# blot-control-board_easyEDA-schematic.net
KiCad netlist of a schematic drawn in EasyEDA
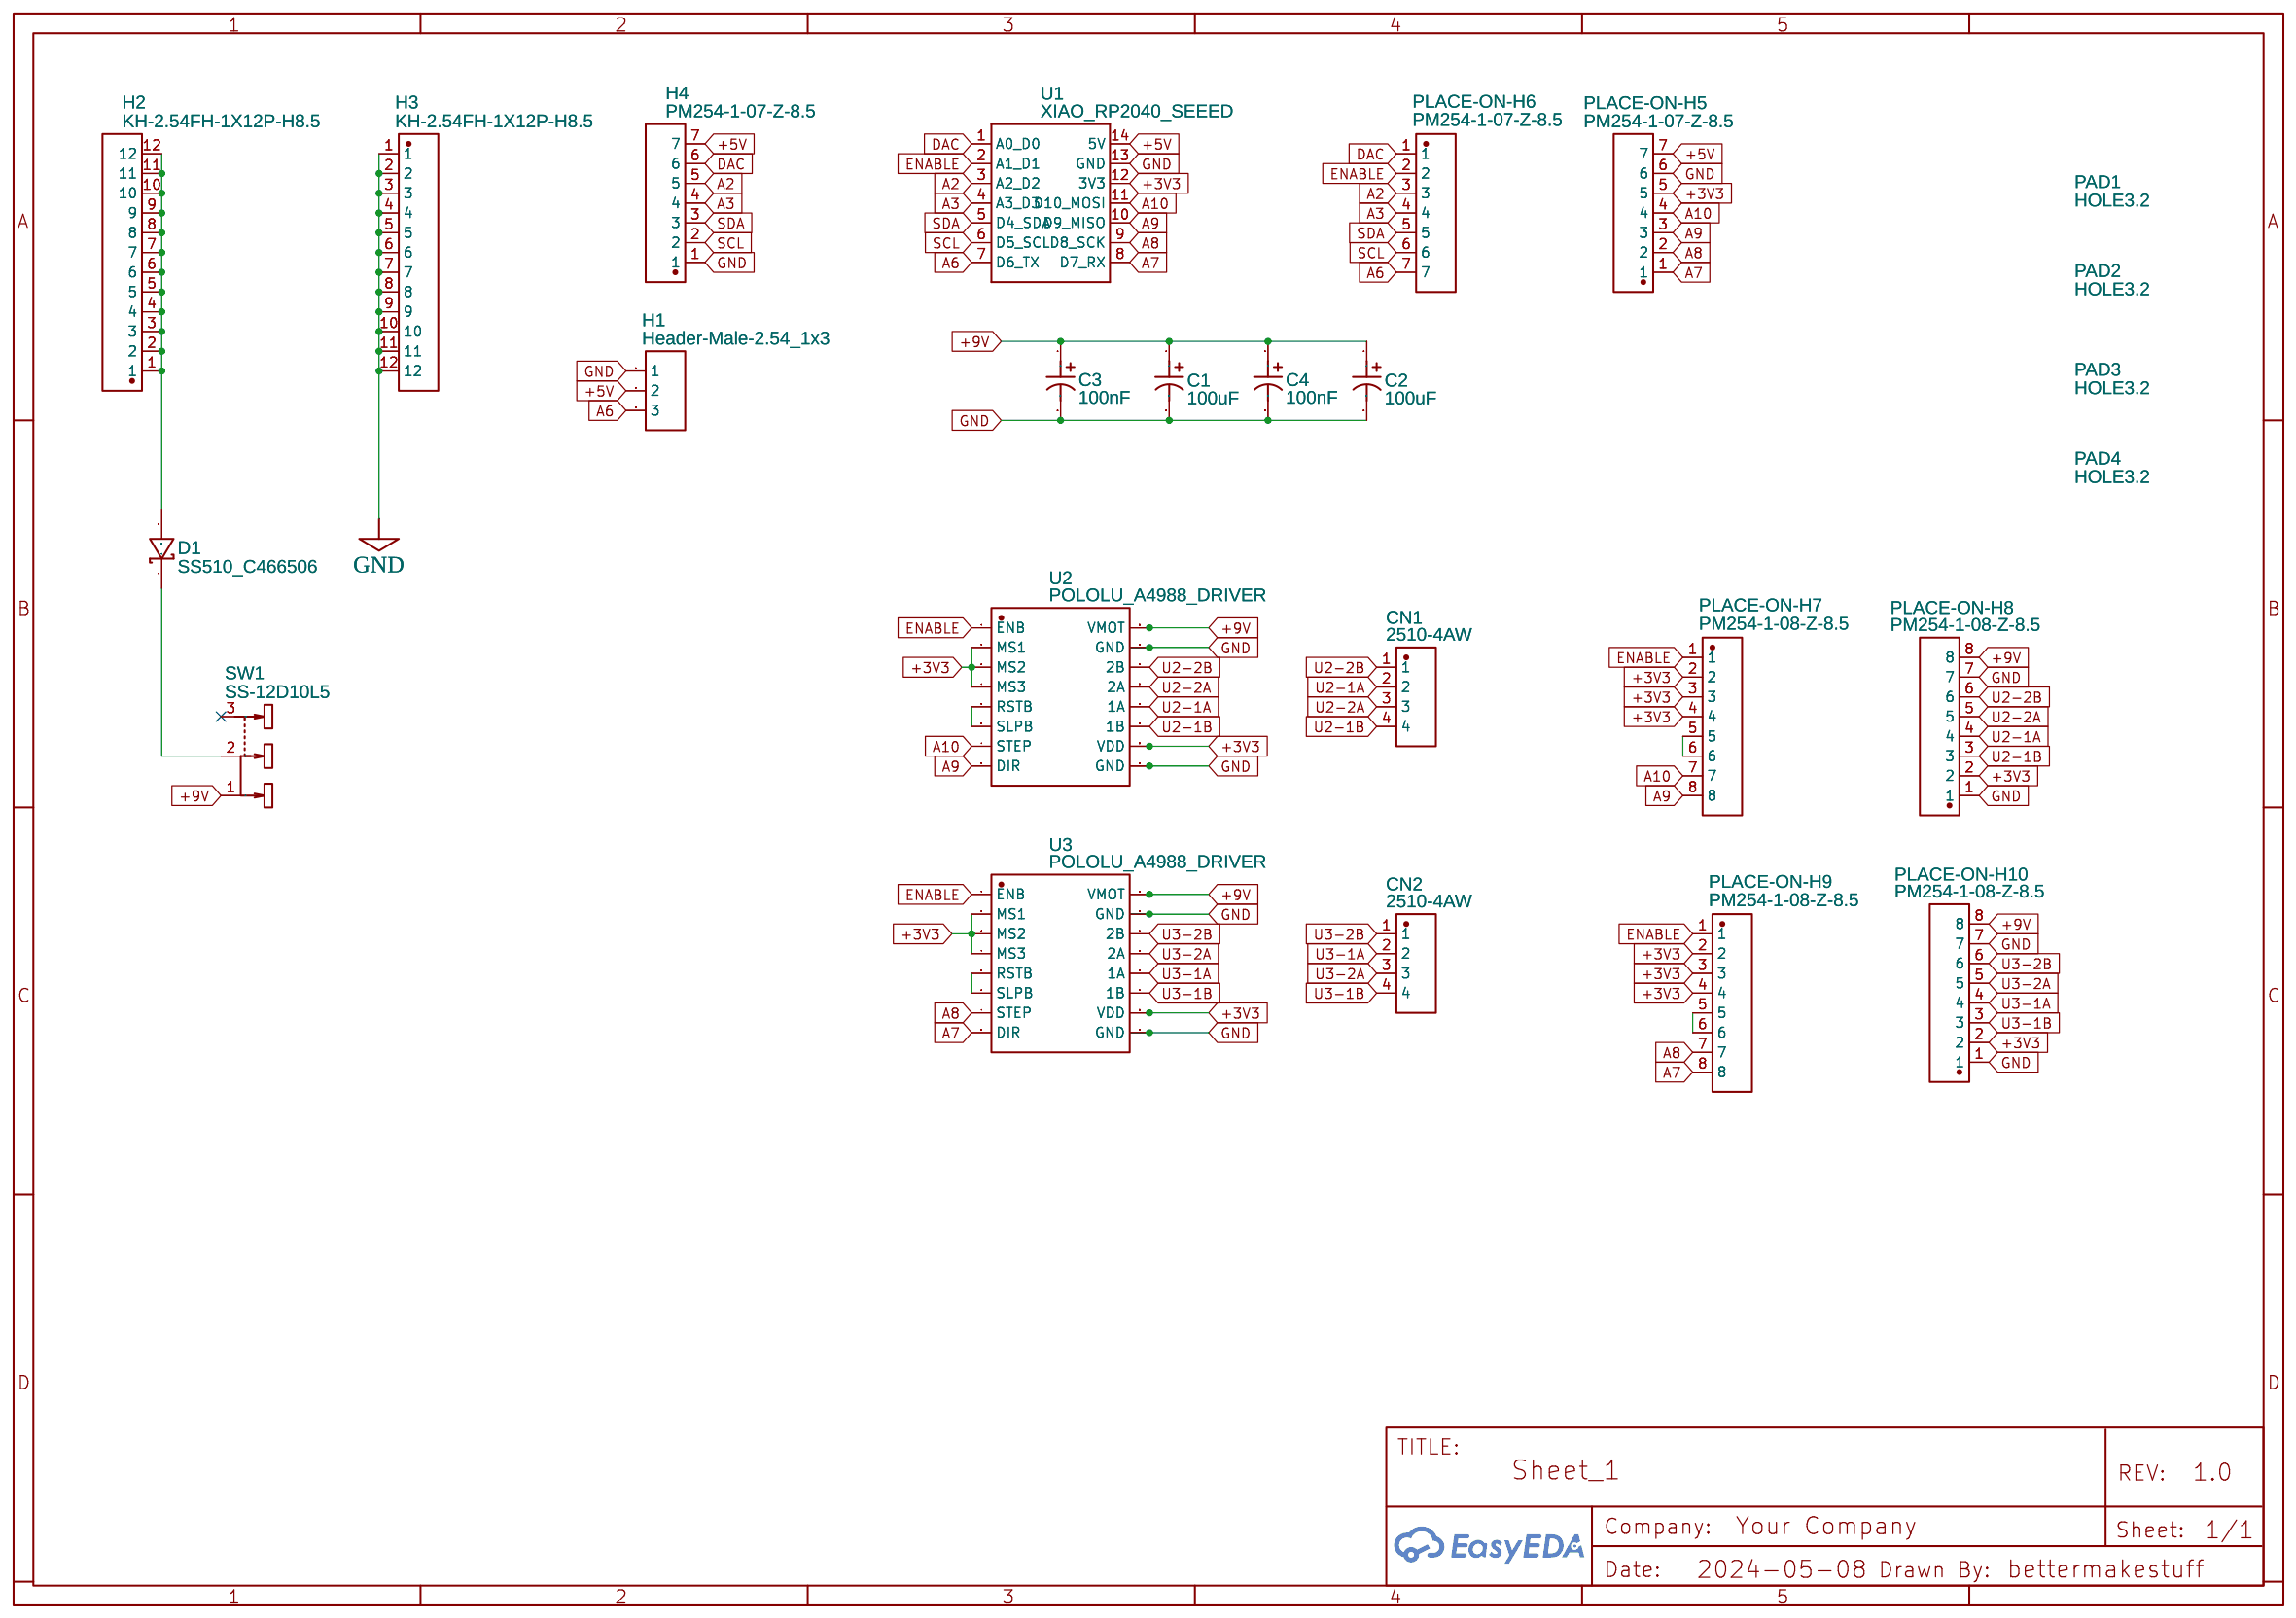
[diagram p0: schematic sheet]

(export (version "E")
  (design (tool "Eeschema 10.0.6"))
  (components
    (comp (ref "C1")
      (value "100uF")
      (fields (field (name "Manufacturer Part") "RST100UF25V004") (field (name "Manufacturer") "KNSCHA(科尼盛)"))
      (libsource (lib "") (part "RST100UF25V004"))
    )
    (comp (ref "C2")
      (value "100uF")
      (fields (field (name "Manufacturer Part") "RST100UF25V004") (field (name "Manufacturer") "KNSCHA(科尼盛)"))
      (libsource (lib "") (part "RST100UF25V004"))
    )
    (comp (ref "C3")
      (value "100nF")
      (fields
        (field (name "Manufacturer Part") "CA45-A-35V-0.1UF-K")
        (field (name "Manufacturer") "CEC(振华新云)")
      )
      (libsource (lib "") (part "CA45-A-35V-0.1UF-K"))
    )
    (comp (ref "C4")
      (value "100nF")
      (fields
        (field (name "Manufacturer Part") "CA45-A-35V-0.1UF-K")
        (field (name "Manufacturer") "CEC(振华新云)")
      )
      (libsource (lib "") (part "CA45-A-35V-0.1UF-K"))
    )
    (comp (ref "CN1")
      (value "2510-4AW")
      (fields (field (name "Manufacturer") "CAX(创都)"))
      (libsource (lib "") (part "2510-4AW"))
    )
    (comp (ref "CN2")
      (value "2510-4AW")
      (fields (field (name "Manufacturer") "CAX(创都)"))
      (libsource (lib "") (part "2510-4AW"))
    )
    (comp (ref "D1")
      (value "SS510_C466506")
      (fields (field (name "Manufacturer Part") "SS510") (field (name "Manufacturer") "High Diode(海德)"))
      (libsource (lib "") (part "SS510_C466506"))
    )
    (comp (ref "H1")
      (value "Header-Male-2.54_1x3")
      (fields (field (name "Manufacturer Part") "2.54-1*3P针") (field (name "Manufacturer") "BOOMELE(博穆精密)"))
      (libsource (lib "") (part "Header-Male-2.54_1x3"))
    )
    (comp (ref "H2")
      (value "KH-2.54FH-1X12P-H8.5")
      (fields (field (name "Manufacturer") "kinghelm(金航标)"))
      (libsource (lib "") (part "KH-2.54FH-1X12P-H8.5"))
    )
    (comp (ref "H3")
      (value "KH-2.54FH-1X12P-H8.5")
      (fields (field (name "Manufacturer") "kinghelm(金航标)"))
      (libsource (lib "") (part "KH-2.54FH-1X12P-H8.5_1"))
    )
    (comp (ref "H4")
      (value "PM254-1-07-Z-8.5")
      (fields (field (name "Manufacturer") "HCTL(华灿天禄)"))
      (libsource (lib "") (part "PM254-1-07-Z-8.5"))
    )
    (comp (ref "PAD1") (value "HOLE3.2") (libsource (lib "") (part "HOLE3.2")))
    (comp (ref "PAD2") (value "HOLE3.2") (libsource (lib "") (part "HOLE3.2")))
    (comp (ref "PAD3") (value "HOLE3.2") (libsource (lib "") (part "HOLE3.2")))
    (comp (ref "PAD4") (value "HOLE3.2") (libsource (lib "") (part "HOLE3.2")))
    (comp (ref "PLACE-ON-H5")
      (value "PM254-1-07-Z-8.5")
      (fields (field (name "Manufacturer") "HCTL(华灿天禄)"))
      (libsource (lib "") (part "PM254-1-07-Z-8.5_2"))
    )
    (comp (ref "PLACE-ON-H6")
      (value "PM254-1-07-Z-8.5")
      (fields (field (name "Manufacturer") "HCTL(华灿天禄)"))
      (libsource (lib "") (part "PM254-1-07-Z-8.5_1"))
    )
    (comp (ref "PLACE-ON-H7")
      (value "PM254-1-08-Z-8.5")
      (fields (field (name "Manufacturer") "HCTL(华灿天禄)"))
      (libsource (lib "") (part "PM254-1-08-Z-8.5"))
    )
    (comp (ref "PLACE-ON-H8")
      (value "PM254-1-08-Z-8.5")
      (fields (field (name "Manufacturer") "HCTL(华灿天禄)"))
      (libsource (lib "") (part "PM254-1-08-Z-8.5_1"))
    )
    (comp (ref "PLACE-ON-H9")
      (value "PM254-1-08-Z-8.5")
      (fields (field (name "Manufacturer") "HCTL(华灿天禄)"))
      (libsource (lib "") (part "PM254-1-08-Z-8.5"))
    )
    (comp (ref "PLACE-ON-H10")
      (value "PM254-1-08-Z-8.5")
      (fields (field (name "Manufacturer") "HCTL(华灿天禄)"))
      (libsource (lib "") (part "PM254-1-08-Z-8.5_1"))
    )
    (comp (ref "SW1")
      (value "SS-12D10L5")
      (fields (field (name "Manufacturer") "XKB Connectivity(中国星坤)"))
      (libsource (lib "") (part "SS-12D10L5"))
    )
    (comp (ref "U1") (value "XIAO_RP2040_SEEED") (libsource (lib "") (part "XIAO_RP2040_SEEED")))
    (comp (ref "U2") (value "POLOLU_A4988_DRIVER") (libsource (lib "") (part "POLOLU_A4988_DRIVER")))
    (comp (ref "U3") (value "POLOLU_A4988_DRIVER") (libsource (lib "") (part "POLOLU_A4988_DRIVER")))
  )
  (nets
    (net (code "1") (name "+3V3") (class "Default")
      (node (ref "PLACE-ON-H10") (pin "2") (pinfunction "2_2") (pintype "unspecified"))
      (node (ref "PLACE-ON-H5") (pin "5") (pinfunction "5_5") (pintype "unspecified"))
      (node (ref "PLACE-ON-H7") (pin "2") (pinfunction "2_2") (pintype "unspecified"))
      (node (ref "PLACE-ON-H7") (pin "3") (pinfunction "3_3") (pintype "unspecified"))
      (node (ref "PLACE-ON-H7") (pin "4") (pinfunction "4_4") (pintype "unspecified"))
      (node (ref "PLACE-ON-H8") (pin "2") (pinfunction "2_2") (pintype "unspecified"))
      (node (ref "PLACE-ON-H9") (pin "2") (pinfunction "2_2") (pintype "unspecified"))
      (node (ref "PLACE-ON-H9") (pin "3") (pinfunction "3_3") (pintype "unspecified"))
      (node (ref "PLACE-ON-H9") (pin "4") (pinfunction "4_4") (pintype "unspecified"))
      (node (ref "U1") (pin "12") (pinfunction "3V3_12") (pintype "bidirectional"))
      (node (ref "U2") (pin "10") (pinfunction "VDD_10") (pintype "unspecified"))
      (node (ref "U2") (pin "2") (pinfunction "MS1_2") (pintype "unspecified"))
      (node (ref "U2") (pin "3") (pinfunction "MS2_3") (pintype "unspecified"))
      (node (ref "U2") (pin "4") (pinfunction "MS3_4") (pintype "unspecified"))
      (node (ref "U3") (pin "10") (pinfunction "VDD_10") (pintype "unspecified"))
      (node (ref "U3") (pin "2") (pinfunction "MS1_2") (pintype "unspecified"))
      (node (ref "U3") (pin "3") (pinfunction "MS2_3") (pintype "unspecified"))
      (node (ref "U3") (pin "4") (pinfunction "MS3_4") (pintype "unspecified"))
    )
    (net (code "2") (name "+5V") (class "Default")
      (node (ref "H1") (pin "2") (pinfunction "2_2") (pintype "input"))
      (node (ref "H4") (pin "7") (pinfunction "7_7") (pintype "unspecified"))
      (node (ref "PLACE-ON-H5") (pin "7") (pinfunction "7_7") (pintype "unspecified"))
      (node (ref "U1") (pin "14") (pinfunction "5V_14") (pintype "bidirectional"))
    )
    (net (code "3") (name "+9V") (class "Default")
      (node (ref "C1") (pin "1") (pinfunction "1_1") (pintype "input"))
      (node (ref "C2") (pin "1") (pinfunction "1_1") (pintype "input"))
      (node (ref "C3") (pin "1") (pinfunction "1_1") (pintype "input"))
      (node (ref "C4") (pin "1") (pinfunction "1_1") (pintype "input"))
      (node (ref "PLACE-ON-H10") (pin "8") (pinfunction "8_8") (pintype "unspecified"))
      (node (ref "PLACE-ON-H8") (pin "8") (pinfunction "8_8") (pintype "unspecified"))
      (node (ref "SW1") (pin "1") (pinfunction "1_1") (pintype "unspecified"))
      (node (ref "U2") (pin "16") (pinfunction "VMOT_16") (pintype "unspecified"))
      (node (ref "U3") (pin "16") (pinfunction "VMOT_16") (pintype "unspecified"))
    )
    (net (code "4") (name "A2") (class "Default")
      (node (ref "H4") (pin "5") (pinfunction "5_5") (pintype "unspecified"))
      (node (ref "PLACE-ON-H6") (pin "3") (pinfunction "3_3") (pintype "unspecified"))
      (node (ref "U1") (pin "3") (pinfunction "A2_D2_3") (pintype "bidirectional"))
    )
    (net (code "5") (name "A3") (class "Default")
      (node (ref "H4") (pin "4") (pinfunction "4_4") (pintype "unspecified"))
      (node (ref "PLACE-ON-H6") (pin "4") (pinfunction "4_4") (pintype "unspecified"))
      (node (ref "U1") (pin "4") (pinfunction "A3_D3_4") (pintype "bidirectional"))
    )
    (net (code "6") (name "A6") (class "Default")
      (node (ref "H1") (pin "3") (pinfunction "3_3") (pintype "input"))
      (node (ref "PLACE-ON-H6") (pin "7") (pinfunction "7_7") (pintype "unspecified"))
      (node (ref "U1") (pin "7") (pinfunction "D6_TX_7") (pintype "bidirectional"))
    )
    (net (code "7") (name "A7") (class "Default")
      (node (ref "PLACE-ON-H5") (pin "1") (pinfunction "1_1") (pintype "unspecified"))
      (node (ref "PLACE-ON-H9") (pin "8") (pinfunction "8_8") (pintype "unspecified"))
      (node (ref "U1") (pin "8") (pinfunction "D7_RX_8") (pintype "bidirectional"))
      (node (ref "U3") (pin "8") (pinfunction "DIR_8") (pintype "unspecified"))
    )
    (net (code "8") (name "A8") (class "Default")
      (node (ref "PLACE-ON-H5") (pin "2") (pinfunction "2_2") (pintype "unspecified"))
      (node (ref "PLACE-ON-H9") (pin "7") (pinfunction "7_7") (pintype "unspecified"))
      (node (ref "U1") (pin "9") (pinfunction "D8_SCK_9") (pintype "bidirectional"))
      (node (ref "U3") (pin "7") (pinfunction "STEP_7") (pintype "unspecified"))
    )
    (net (code "9") (name "A9") (class "Default")
      (node (ref "PLACE-ON-H5") (pin "3") (pinfunction "3_3") (pintype "unspecified"))
      (node (ref "PLACE-ON-H7") (pin "8") (pinfunction "8_8") (pintype "unspecified"))
      (node (ref "U1") (pin "10") (pinfunction "D9_MISO_10") (pintype "bidirectional"))
      (node (ref "U2") (pin "8") (pinfunction "DIR_8") (pintype "unspecified"))
    )
    (net (code "10") (name "A10") (class "Default")
      (node (ref "PLACE-ON-H5") (pin "4") (pinfunction "4_4") (pintype "unspecified"))
      (node (ref "PLACE-ON-H7") (pin "7") (pinfunction "7_7") (pintype "unspecified"))
      (node (ref "U1") (pin "11") (pinfunction "D10_MOSI_11") (pintype "bidirectional"))
      (node (ref "U2") (pin "7") (pinfunction "STEP_7") (pintype "unspecified"))
    )
    (net (code "11") (name "DAC") (class "Default")
      (node (ref "H4") (pin "6") (pinfunction "6_6") (pintype "unspecified"))
      (node (ref "PLACE-ON-H6") (pin "1") (pinfunction "1_1") (pintype "unspecified"))
      (node (ref "U1") (pin "1") (pinfunction "A0_D0_1") (pintype "bidirectional"))
    )
    (net (code "12") (name "ENABLE") (class "Default")
      (node (ref "PLACE-ON-H6") (pin "2") (pinfunction "2_2") (pintype "unspecified"))
      (node (ref "PLACE-ON-H7") (pin "1") (pinfunction "1_1") (pintype "unspecified"))
      (node (ref "PLACE-ON-H9") (pin "1") (pinfunction "1_1") (pintype "unspecified"))
      (node (ref "U1") (pin "2") (pinfunction "A1_D1_2") (pintype "bidirectional"))
      (node (ref "U2") (pin "1") (pinfunction "ENB_1") (pintype "unspecified"))
      (node (ref "U3") (pin "1") (pinfunction "ENB_1") (pintype "unspecified"))
    )
    (net (code "13") (name "GND") (class "Default")
      (node (ref "C1") (pin "2") (pinfunction "2_2") (pintype "input"))
      (node (ref "C2") (pin "2") (pinfunction "2_2") (pintype "input"))
      (node (ref "C3") (pin "2") (pinfunction "2_2") (pintype "input"))
      (node (ref "C4") (pin "2") (pinfunction "2_2") (pintype "input"))
      (node (ref "H1") (pin "1") (pinfunction "1_1") (pintype "input"))
      (node (ref "H3") (pin "1") (pinfunction "1_1") (pintype "unspecified"))
      (node (ref "H3") (pin "10") (pinfunction "10_10") (pintype "unspecified"))
      (node (ref "H3") (pin "11") (pinfunction "11_11") (pintype "unspecified"))
      (node (ref "H3") (pin "12") (pinfunction "12_12") (pintype "unspecified"))
      (node (ref "H3") (pin "2") (pinfunction "2_2") (pintype "unspecified"))
      (node (ref "H3") (pin "3") (pinfunction "3_3") (pintype "unspecified"))
      (node (ref "H3") (pin "4") (pinfunction "4_4") (pintype "unspecified"))
      (node (ref "H3") (pin "5") (pinfunction "5_5") (pintype "unspecified"))
      (node (ref "H3") (pin "6") (pinfunction "6_6") (pintype "unspecified"))
      (node (ref "H3") (pin "7") (pinfunction "7_7") (pintype "unspecified"))
      (node (ref "H3") (pin "8") (pinfunction "8_8") (pintype "unspecified"))
      (node (ref "H3") (pin "9") (pinfunction "9_9") (pintype "unspecified"))
      (node (ref "H4") (pin "1") (pinfunction "1_1") (pintype "unspecified"))
      (node (ref "PLACE-ON-H10") (pin "1") (pinfunction "1_1") (pintype "unspecified"))
      (node (ref "PLACE-ON-H10") (pin "7") (pinfunction "7_7") (pintype "unspecified"))
      (node (ref "PLACE-ON-H5") (pin "6") (pinfunction "6_6") (pintype "unspecified"))
      (node (ref "PLACE-ON-H8") (pin "1") (pinfunction "1_1") (pintype "unspecified"))
      (node (ref "PLACE-ON-H8") (pin "7") (pinfunction "7_7") (pintype "unspecified"))
      (node (ref "U1") (pin "13") (pinfunction "GND_13") (pintype "bidirectional"))
      (node (ref "U2") (pin "15") (pinfunction "GND_15") (pintype "unspecified"))
      (node (ref "U2") (pin "9") (pinfunction "GND_9") (pintype "unspecified"))
      (node (ref "U3") (pin "15") (pinfunction "GND_15") (pintype "unspecified"))
      (node (ref "U3") (pin "9") (pinfunction "GND_9") (pintype "unspecified"))
    )
    (net (code "14") (name "Net-(D1-Pad1)") (class "Default")
      (node (ref "D1") (pin "1") (pinfunction "1_1") (pintype "unspecified"))
      (node (ref "SW1") (pin "2") (pinfunction "2_2") (pintype "unspecified"))
    )
    (net (code "15") (name "Net-(D1-Pad2)") (class "Default")
      (node (ref "D1") (pin "2") (pinfunction "2_2") (pintype "unspecified"))
      (node (ref "H2") (pin "1") (pinfunction "1_1") (pintype "unspecified"))
      (node (ref "H2") (pin "10") (pinfunction "10_10") (pintype "unspecified"))
      (node (ref "H2") (pin "11") (pinfunction "11_11") (pintype "unspecified"))
      (node (ref "H2") (pin "12") (pinfunction "12_12") (pintype "unspecified"))
      (node (ref "H2") (pin "2") (pinfunction "2_2") (pintype "unspecified"))
      (node (ref "H2") (pin "3") (pinfunction "3_3") (pintype "unspecified"))
      (node (ref "H2") (pin "4") (pinfunction "4_4") (pintype "unspecified"))
      (node (ref "H2") (pin "5") (pinfunction "5_5") (pintype "unspecified"))
      (node (ref "H2") (pin "6") (pinfunction "6_6") (pintype "unspecified"))
      (node (ref "H2") (pin "7") (pinfunction "7_7") (pintype "unspecified"))
      (node (ref "H2") (pin "8") (pinfunction "8_8") (pintype "unspecified"))
      (node (ref "H2") (pin "9") (pinfunction "9_9") (pintype "unspecified"))
    )
    (net (code "16") (name "Net-(PLACE-ON-H7-Pad5)") (class "Default")
      (node (ref "PLACE-ON-H7") (pin "5") (pinfunction "5_5") (pintype "unspecified"))
      (node (ref "PLACE-ON-H7") (pin "6") (pinfunction "6_6") (pintype "unspecified"))
    )
    (net (code "17") (name "Net-(PLACE-ON-H9-Pad5)") (class "Default")
      (node (ref "PLACE-ON-H9") (pin "5") (pinfunction "5_5") (pintype "unspecified"))
      (node (ref "PLACE-ON-H9") (pin "6") (pinfunction "6_6") (pintype "unspecified"))
    )
    (net (code "18") (name "Net-(U2-RSTB)") (class "Default")
      (node (ref "U2") (pin "5") (pinfunction "RSTB_5") (pintype "unspecified"))
      (node (ref "U2") (pin "6") (pinfunction "SLPB_6") (pintype "unspecified"))
    )
    (net (code "19") (name "Net-(U3-RSTB)") (class "Default")
      (node (ref "U3") (pin "5") (pinfunction "RSTB_5") (pintype "unspecified"))
      (node (ref "U3") (pin "6") (pinfunction "SLPB_6") (pintype "unspecified"))
    )
    (net (code "20") (name "SCL") (class "Default")
      (node (ref "H4") (pin "2") (pinfunction "2_2") (pintype "unspecified"))
      (node (ref "PLACE-ON-H6") (pin "6") (pinfunction "6_6") (pintype "unspecified"))
      (node (ref "U1") (pin "6") (pinfunction "D5_SCL_6") (pintype "bidirectional"))
    )
    (net (code "21") (name "SDA") (class "Default")
      (node (ref "H4") (pin "3") (pinfunction "3_3") (pintype "unspecified"))
      (node (ref "PLACE-ON-H6") (pin "5") (pinfunction "5_5") (pintype "unspecified"))
      (node (ref "U1") (pin "5") (pinfunction "D4_SDA_5") (pintype "bidirectional"))
    )
    (net (code "22") (name "U2-1A") (class "Default")
      (node (ref "CN1") (pin "2") (pinfunction "2_2") (pintype "unspecified"))
      (node (ref "PLACE-ON-H8") (pin "4") (pinfunction "4_4") (pintype "unspecified"))
      (node (ref "U2") (pin "12") (pinfunction "1A_12") (pintype "unspecified"))
    )
    (net (code "23") (name "U2-1B") (class "Default")
      (node (ref "CN1") (pin "4") (pinfunction "4_4") (pintype "unspecified"))
      (node (ref "PLACE-ON-H8") (pin "3") (pinfunction "3_3") (pintype "unspecified"))
      (node (ref "U2") (pin "11") (pinfunction "1B_11") (pintype "unspecified"))
    )
    (net (code "24") (name "U2-2A") (class "Default")
      (node (ref "CN1") (pin "3") (pinfunction "3_3") (pintype "unspecified"))
      (node (ref "PLACE-ON-H8") (pin "5") (pinfunction "5_5") (pintype "unspecified"))
      (node (ref "U2") (pin "13") (pinfunction "2A_13") (pintype "unspecified"))
    )
    (net (code "25") (name "U2-2B") (class "Default")
      (node (ref "CN1") (pin "1") (pinfunction "1_1") (pintype "unspecified"))
      (node (ref "PLACE-ON-H8") (pin "6") (pinfunction "6_6") (pintype "unspecified"))
      (node (ref "U2") (pin "14") (pinfunction "2B_14") (pintype "unspecified"))
    )
    (net (code "26") (name "U3-1A") (class "Default")
      (node (ref "CN2") (pin "2") (pinfunction "2_2") (pintype "unspecified"))
      (node (ref "PLACE-ON-H10") (pin "4") (pinfunction "4_4") (pintype "unspecified"))
      (node (ref "U3") (pin "12") (pinfunction "1A_12") (pintype "unspecified"))
    )
    (net (code "27") (name "U3-1B") (class "Default")
      (node (ref "CN2") (pin "4") (pinfunction "4_4") (pintype "unspecified"))
      (node (ref "PLACE-ON-H10") (pin "3") (pinfunction "3_3") (pintype "unspecified"))
      (node (ref "U3") (pin "11") (pinfunction "1B_11") (pintype "unspecified"))
    )
    (net (code "28") (name "U3-2A") (class "Default")
      (node (ref "CN2") (pin "3") (pinfunction "3_3") (pintype "unspecified"))
      (node (ref "PLACE-ON-H10") (pin "5") (pinfunction "5_5") (pintype "unspecified"))
      (node (ref "U3") (pin "13") (pinfunction "2A_13") (pintype "unspecified"))
    )
    (net (code "29") (name "U3-2B") (class "Default")
      (node (ref "CN2") (pin "1") (pinfunction "1_1") (pintype "unspecified"))
      (node (ref "PLACE-ON-H10") (pin "6") (pinfunction "6_6") (pintype "unspecified"))
      (node (ref "U3") (pin "14") (pinfunction "2B_14") (pintype "unspecified"))
    )
    (net (code "30") (name "unconnected-(SW1-Pad3)") (class "Default")
      (node (ref "SW1") (pin "3") (pinfunction "3_3") (pintype "unspecified+no_connect"))
    )
  )
)
